# NAND8_GENERIC.net
KiCad netlist of a schematic drawn in Altium Designer
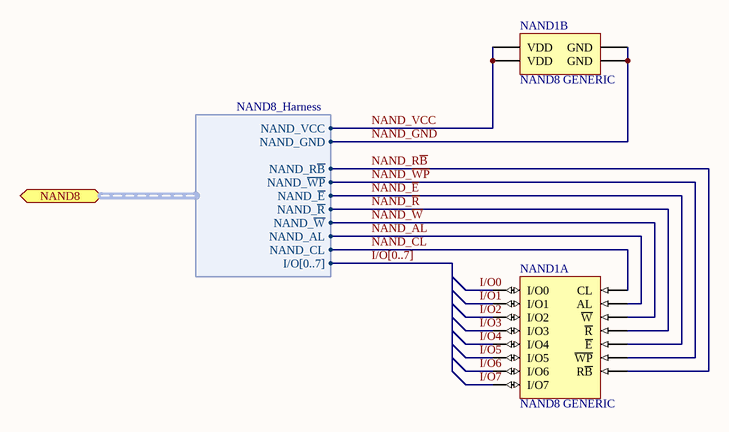
[diagram p0: NAND8_GENERIC.SchDoc]

(export (version "E")
  (design (tool "Eeschema 10.0.6"))
  (components
    (comp (ref "NAND1")
      (value "NAND8 GENERIC")
      (footprint "TSOP48")
      (libsource (lib "MyLibAltium_v1") (part "NAND8 GENERIC"))
    )
  )
  (nets
    (net (code "2") (name "/I{slash}O0") (class "Default")
      (node (ref "NAND1") (pin "29") (pinfunction "I/O0_29") (pintype "bidirectional"))
    )
    (net (code "3") (name "/I{slash}O1") (class "Default")
      (node (ref "NAND1") (pin "30") (pinfunction "I/O1_30") (pintype "bidirectional"))
    )
    (net (code "4") (name "/I{slash}O2") (class "Default")
      (node (ref "NAND1") (pin "31") (pinfunction "I/O2_31") (pintype "bidirectional"))
    )
    (net (code "5") (name "/I{slash}O3") (class "Default")
      (node (ref "NAND1") (pin "32") (pinfunction "I/O3_32") (pintype "bidirectional"))
    )
    (net (code "6") (name "/I{slash}O4") (class "Default")
      (node (ref "NAND1") (pin "41") (pinfunction "I/O4_41") (pintype "bidirectional"))
    )
    (net (code "7") (name "/I{slash}O5") (class "Default")
      (node (ref "NAND1") (pin "42") (pinfunction "I/O5_42") (pintype "bidirectional"))
    )
    (net (code "8") (name "/I{slash}O6") (class "Default")
      (node (ref "NAND1") (pin "43") (pinfunction "I/O6_43") (pintype "bidirectional"))
    )
    (net (code "9") (name "/I{slash}O7") (class "Default")
      (node (ref "NAND1") (pin "44") (pinfunction "I/O7_44") (pintype "bidirectional"))
    )
    (net (code "11") (name "/NAND_AL") (class "Default")
      (node (ref "NAND1") (pin "17") (pinfunction "AL_17") (pintype "input"))
    )
    (net (code "12") (name "/NAND_CL") (class "Default")
      (node (ref "NAND1") (pin "16") (pinfunction "CL_16") (pintype "input"))
    )
    (net (code "13") (name "/NAND_GND") (class "Default")
      (node (ref "NAND1") (pin "13") (pinfunction "GND_13") (pintype "power_in"))
      (node (ref "NAND1") (pin "36") (pinfunction "GND_36") (pintype "power_in"))
    )
    (net (code "14") (name "/NAND_R~{B}") (class "Default")
      (node (ref "NAND1") (pin "7") (pinfunction "R~{B}_7") (pintype "input"))
    )
    (net (code "15") (name "/NAND_VCC") (class "Default")
      (node (ref "NAND1") (pin "12") (pinfunction "VDD_12") (pintype "power_in"))
      (node (ref "NAND1") (pin "37") (pinfunction "VDD_37") (pintype "power_in"))
    )
    (net (code "16") (name "/NAND_~{E}") (class "Default")
      (node (ref "NAND1") (pin "9") (pinfunction "~{E}_9") (pintype "input"))
    )
    (net (code "17") (name "/NAND_~{R}") (class "Default")
      (node (ref "NAND1") (pin "8") (pinfunction "~{R}_8") (pintype "input"))
    )
    (net (code "18") (name "/NAND_~{WP}") (class "Default")
      (node (ref "NAND1") (pin "19") (pinfunction "~{WP}_19") (pintype "input"))
    )
    (net (code "19") (name "/NAND_~{W}") (class "Default")
      (node (ref "NAND1") (pin "18") (pinfunction "~{W}_18") (pintype "input"))
    )
  )
)
